# MODULO1.net
KiCad netlist of a schematic drawn in EAGLE
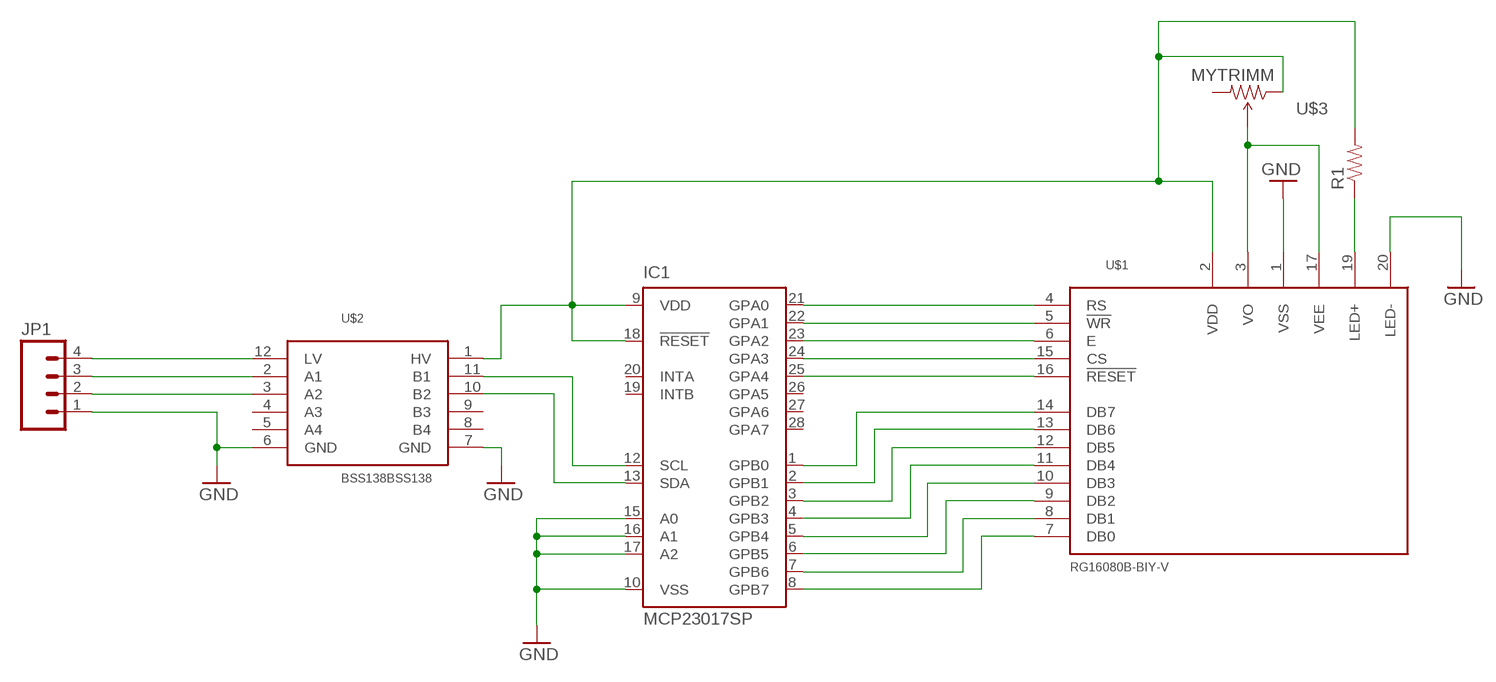
[diagram p0: schematic, sheet 1]

(export (version "E")
  (design (tool "Eeschema 10.0.6"))
  (components
    (comp (ref "IC1")
      (value "MCP23017SP")
      (footprint "eagle-import:DIL28-3")
      (fields (field (name "MF") "MICROCHIP") (field (name "MPN") "MCP23017-E/SP"))
      (libsource (lib "eagle-import") (part "MCP23017SP"))
    )
    (comp (ref "JP1")
      (value "M04PTH")
      (footprint "eagle-import:1X04")
      (libsource (lib "eagle-import") (part "M04PTH"))
    )
    (comp (ref "R1")
      (value "RESISTOR0805-RES")
      (footprint "eagle-import:0805")
      (libsource (lib "eagle-import") (part "RESISTOR0805-RES"))
    )
    (comp (ref "U$1")
      (value "RG16080B-BIY-V")
      (footprint "eagle-import:1X20")
      (libsource (lib "eagle-import") (part "RG16080B-BIY-V"))
    )
    (comp (ref "U$2")
      (value "BSS138BSS138")
      (footprint "eagle-import:BSS138")
      (libsource (lib "eagle-import") (part "BSS138BSS138"))
    )
    (comp (ref "U$3")
      (value "MYTRIMM")
      (footprint "eagle-import:MYTRIMM")
      (libsource (lib "eagle-import") (part "MYTRIMM"))
    )
  )
  (nets
    (net (code "1") (name "GND") (class "Default")
      (node (ref "IC1") (pin "10") (pinfunction "VSS_10") (pintype "power_in"))
      (node (ref "IC1") (pin "15") (pinfunction "A0_15") (pintype "input"))
      (node (ref "IC1") (pin "16") (pinfunction "A1_16") (pintype "input"))
      (node (ref "IC1") (pin "17") (pinfunction "A2_17") (pintype "input"))
      (node (ref "JP1") (pin "1") (pinfunction "1_1") (pintype "passive"))
      (node (ref "U$1") (pin "1") (pinfunction "VSS_1") (pintype "power_in"))
      (node (ref "U$1") (pin "20") (pinfunction "LED-_20") (pintype "bidirectional"))
      (node (ref "U$2") (pin "6") (pinfunction "GND_6") (pintype "power_in"))
      (node (ref "U$2") (pin "7") (pinfunction "GND_7") (pintype "power_in"))
    )
    (net (code "2") (name "Net-(IC1-GPA0)") (class "Default")
      (node (ref "IC1") (pin "21") (pinfunction "GPA0_21") (pintype "bidirectional"))
      (node (ref "U$1") (pin "4") (pinfunction "RS_4") (pintype "bidirectional"))
    )
    (net (code "3") (name "Net-(IC1-GPA1)") (class "Default")
      (node (ref "IC1") (pin "22") (pinfunction "GPA1_22") (pintype "bidirectional"))
      (node (ref "U$1") (pin "5") (pinfunction "~{WR}_5") (pintype "bidirectional"))
    )
    (net (code "4") (name "Net-(IC1-GPA2)") (class "Default")
      (node (ref "IC1") (pin "23") (pinfunction "GPA2_23") (pintype "bidirectional"))
      (node (ref "U$1") (pin "6") (pinfunction "E_6") (pintype "bidirectional"))
    )
    (net (code "5") (name "Net-(IC1-GPA3)") (class "Default")
      (node (ref "IC1") (pin "24") (pinfunction "GPA3_24") (pintype "bidirectional"))
      (node (ref "U$1") (pin "15") (pinfunction "CS_15") (pintype "bidirectional"))
    )
    (net (code "6") (name "Net-(IC1-GPA4)") (class "Default")
      (node (ref "IC1") (pin "25") (pinfunction "GPA4_25") (pintype "bidirectional"))
      (node (ref "U$1") (pin "16") (pinfunction "~{RESET}_16") (pintype "bidirectional"))
    )
    (net (code "7") (name "Net-(IC1-GPB0)") (class "Default")
      (node (ref "IC1") (pin "1") (pinfunction "GPB0_1") (pintype "bidirectional"))
      (node (ref "U$1") (pin "14") (pinfunction "DB7_14") (pintype "bidirectional"))
    )
    (net (code "8") (name "Net-(IC1-GPB1)") (class "Default")
      (node (ref "IC1") (pin "2") (pinfunction "GPB1_2") (pintype "bidirectional"))
      (node (ref "U$1") (pin "13") (pinfunction "DB6_13") (pintype "bidirectional"))
    )
    (net (code "9") (name "Net-(IC1-GPB2)") (class "Default")
      (node (ref "IC1") (pin "3") (pinfunction "GPB2_3") (pintype "bidirectional"))
      (node (ref "U$1") (pin "12") (pinfunction "DB5_12") (pintype "bidirectional"))
    )
    (net (code "10") (name "Net-(IC1-GPB3)") (class "Default")
      (node (ref "IC1") (pin "4") (pinfunction "GPB3_4") (pintype "bidirectional"))
      (node (ref "U$1") (pin "11") (pinfunction "DB4_11") (pintype "bidirectional"))
    )
    (net (code "11") (name "Net-(IC1-GPB4)") (class "Default")
      (node (ref "IC1") (pin "5") (pinfunction "GPB4_5") (pintype "bidirectional"))
      (node (ref "U$1") (pin "10") (pinfunction "DB3_10") (pintype "bidirectional"))
    )
    (net (code "12") (name "Net-(IC1-GPB5)") (class "Default")
      (node (ref "IC1") (pin "6") (pinfunction "GPB5_6") (pintype "bidirectional"))
      (node (ref "U$1") (pin "9") (pinfunction "DB2_9") (pintype "bidirectional"))
    )
    (net (code "13") (name "Net-(IC1-GPB6)") (class "Default")
      (node (ref "IC1") (pin "7") (pinfunction "GPB6_7") (pintype "bidirectional"))
      (node (ref "U$1") (pin "8") (pinfunction "DB1_8") (pintype "bidirectional"))
    )
    (net (code "14") (name "Net-(IC1-GPB7)") (class "Default")
      (node (ref "IC1") (pin "8") (pinfunction "GPB7_8") (pintype "bidirectional"))
      (node (ref "U$1") (pin "7") (pinfunction "DB0_7") (pintype "bidirectional"))
    )
    (net (code "15") (name "Net-(IC1-SCL)") (class "Default")
      (node (ref "IC1") (pin "12") (pinfunction "SCL_12") (pintype "input"))
      (node (ref "U$2") (pin "11") (pinfunction "B1_11") (pintype "bidirectional"))
    )
    (net (code "16") (name "Net-(IC1-SDA)") (class "Default")
      (node (ref "IC1") (pin "13") (pinfunction "SDA_13") (pintype "bidirectional"))
      (node (ref "U$2") (pin "10") (pinfunction "B2_10") (pintype "bidirectional"))
    )
    (net (code "17") (name "Net-(IC1-VDD)") (class "Default")
      (node (ref "IC1") (pin "18") (pinfunction "~{RESET}_18") (pintype "input"))
      (node (ref "IC1") (pin "9") (pinfunction "VDD_9") (pintype "power_in"))
      (node (ref "R1") (pin "2") (pinfunction "2_2") (pintype "passive"))
      (node (ref "U$1") (pin "2") (pinfunction "VDD_2") (pintype "power_in"))
      (node (ref "U$2") (pin "1") (pinfunction "HV_1") (pintype "power_in"))
      (node (ref "U$3") (pin "1") (pinfunction "CCW_1") (pintype "passive"))
    )
    (net (code "18") (name "Net-(U$1-LED+)") (class "Default")
      (node (ref "R1") (pin "1") (pinfunction "1_1") (pintype "passive"))
      (node (ref "U$1") (pin "19") (pinfunction "LED+_19") (pintype "bidirectional"))
    )
    (net (code "19") (name "Net-(U$1-VEE)") (class "Default")
      (node (ref "U$1") (pin "17") (pinfunction "VEE_17") (pintype "power_in"))
      (node (ref "U$1") (pin "3") (pinfunction "VO_3") (pintype "power_in"))
      (node (ref "U$3") (pin "2") (pinfunction "WIPER_2") (pintype "passive"))
    )
    (net (code "20") (name "Net-(U$2-A1)") (class "Default")
      (node (ref "JP1") (pin "3") (pinfunction "3_3") (pintype "passive"))
      (node (ref "U$2") (pin "2") (pinfunction "A1_2") (pintype "bidirectional"))
    )
    (net (code "21") (name "Net-(U$2-A2)") (class "Default")
      (node (ref "JP1") (pin "2") (pinfunction "2_2") (pintype "passive"))
      (node (ref "U$2") (pin "3") (pinfunction "A2_3") (pintype "bidirectional"))
    )
    (net (code "22") (name "Net-(U$2-LV)") (class "Default")
      (node (ref "JP1") (pin "4") (pinfunction "4_4") (pintype "passive"))
      (node (ref "U$2") (pin "12") (pinfunction "LV_12") (pintype "power_in"))
    )
    (net (code "23") (name "unconnected-(IC1-GPA5-Pad26)") (class "Default")
      (node (ref "IC1") (pin "26") (pinfunction "GPA5_26") (pintype "bidirectional"))
    )
    (net (code "24") (name "unconnected-(IC1-GPA6-Pad27)") (class "Default")
      (node (ref "IC1") (pin "27") (pinfunction "GPA6_27") (pintype "bidirectional"))
    )
    (net (code "25") (name "unconnected-(IC1-GPA7-Pad28)") (class "Default")
      (node (ref "IC1") (pin "28") (pinfunction "GPA7_28") (pintype "bidirectional"))
    )
    (net (code "26") (name "unconnected-(IC1-INTA-Pad20)") (class "Default")
      (node (ref "IC1") (pin "20") (pinfunction "INTA_20") (pintype "output"))
    )
    (net (code "27") (name "unconnected-(IC1-INTB-Pad19)") (class "Default")
      (node (ref "IC1") (pin "19") (pinfunction "INTB_19") (pintype "output"))
    )
    (net (code "28") (name "unconnected-(U$2-A3-Pad4)") (class "Default")
      (node (ref "U$2") (pin "4") (pinfunction "A3_4") (pintype "bidirectional"))
    )
    (net (code "29") (name "unconnected-(U$2-A4-Pad5)") (class "Default")
      (node (ref "U$2") (pin "5") (pinfunction "A4_5") (pintype "bidirectional"))
    )
    (net (code "30") (name "unconnected-(U$2-B3-Pad9)") (class "Default")
      (node (ref "U$2") (pin "9") (pinfunction "B3_9") (pintype "bidirectional"))
    )
    (net (code "31") (name "unconnected-(U$2-B4-Pad8)") (class "Default")
      (node (ref "U$2") (pin "8") (pinfunction "B4_8") (pintype "bidirectional"))
    )
    (net (code "32") (name "unconnected-(U$3-CW-Pad3)") (class "Default")
      (node (ref "U$3") (pin "3") (pinfunction "CW_3") (pintype "passive"))
    )
  )
)
